# startracker.net
KiCad netlist of a schematic drawn in EasyEDA
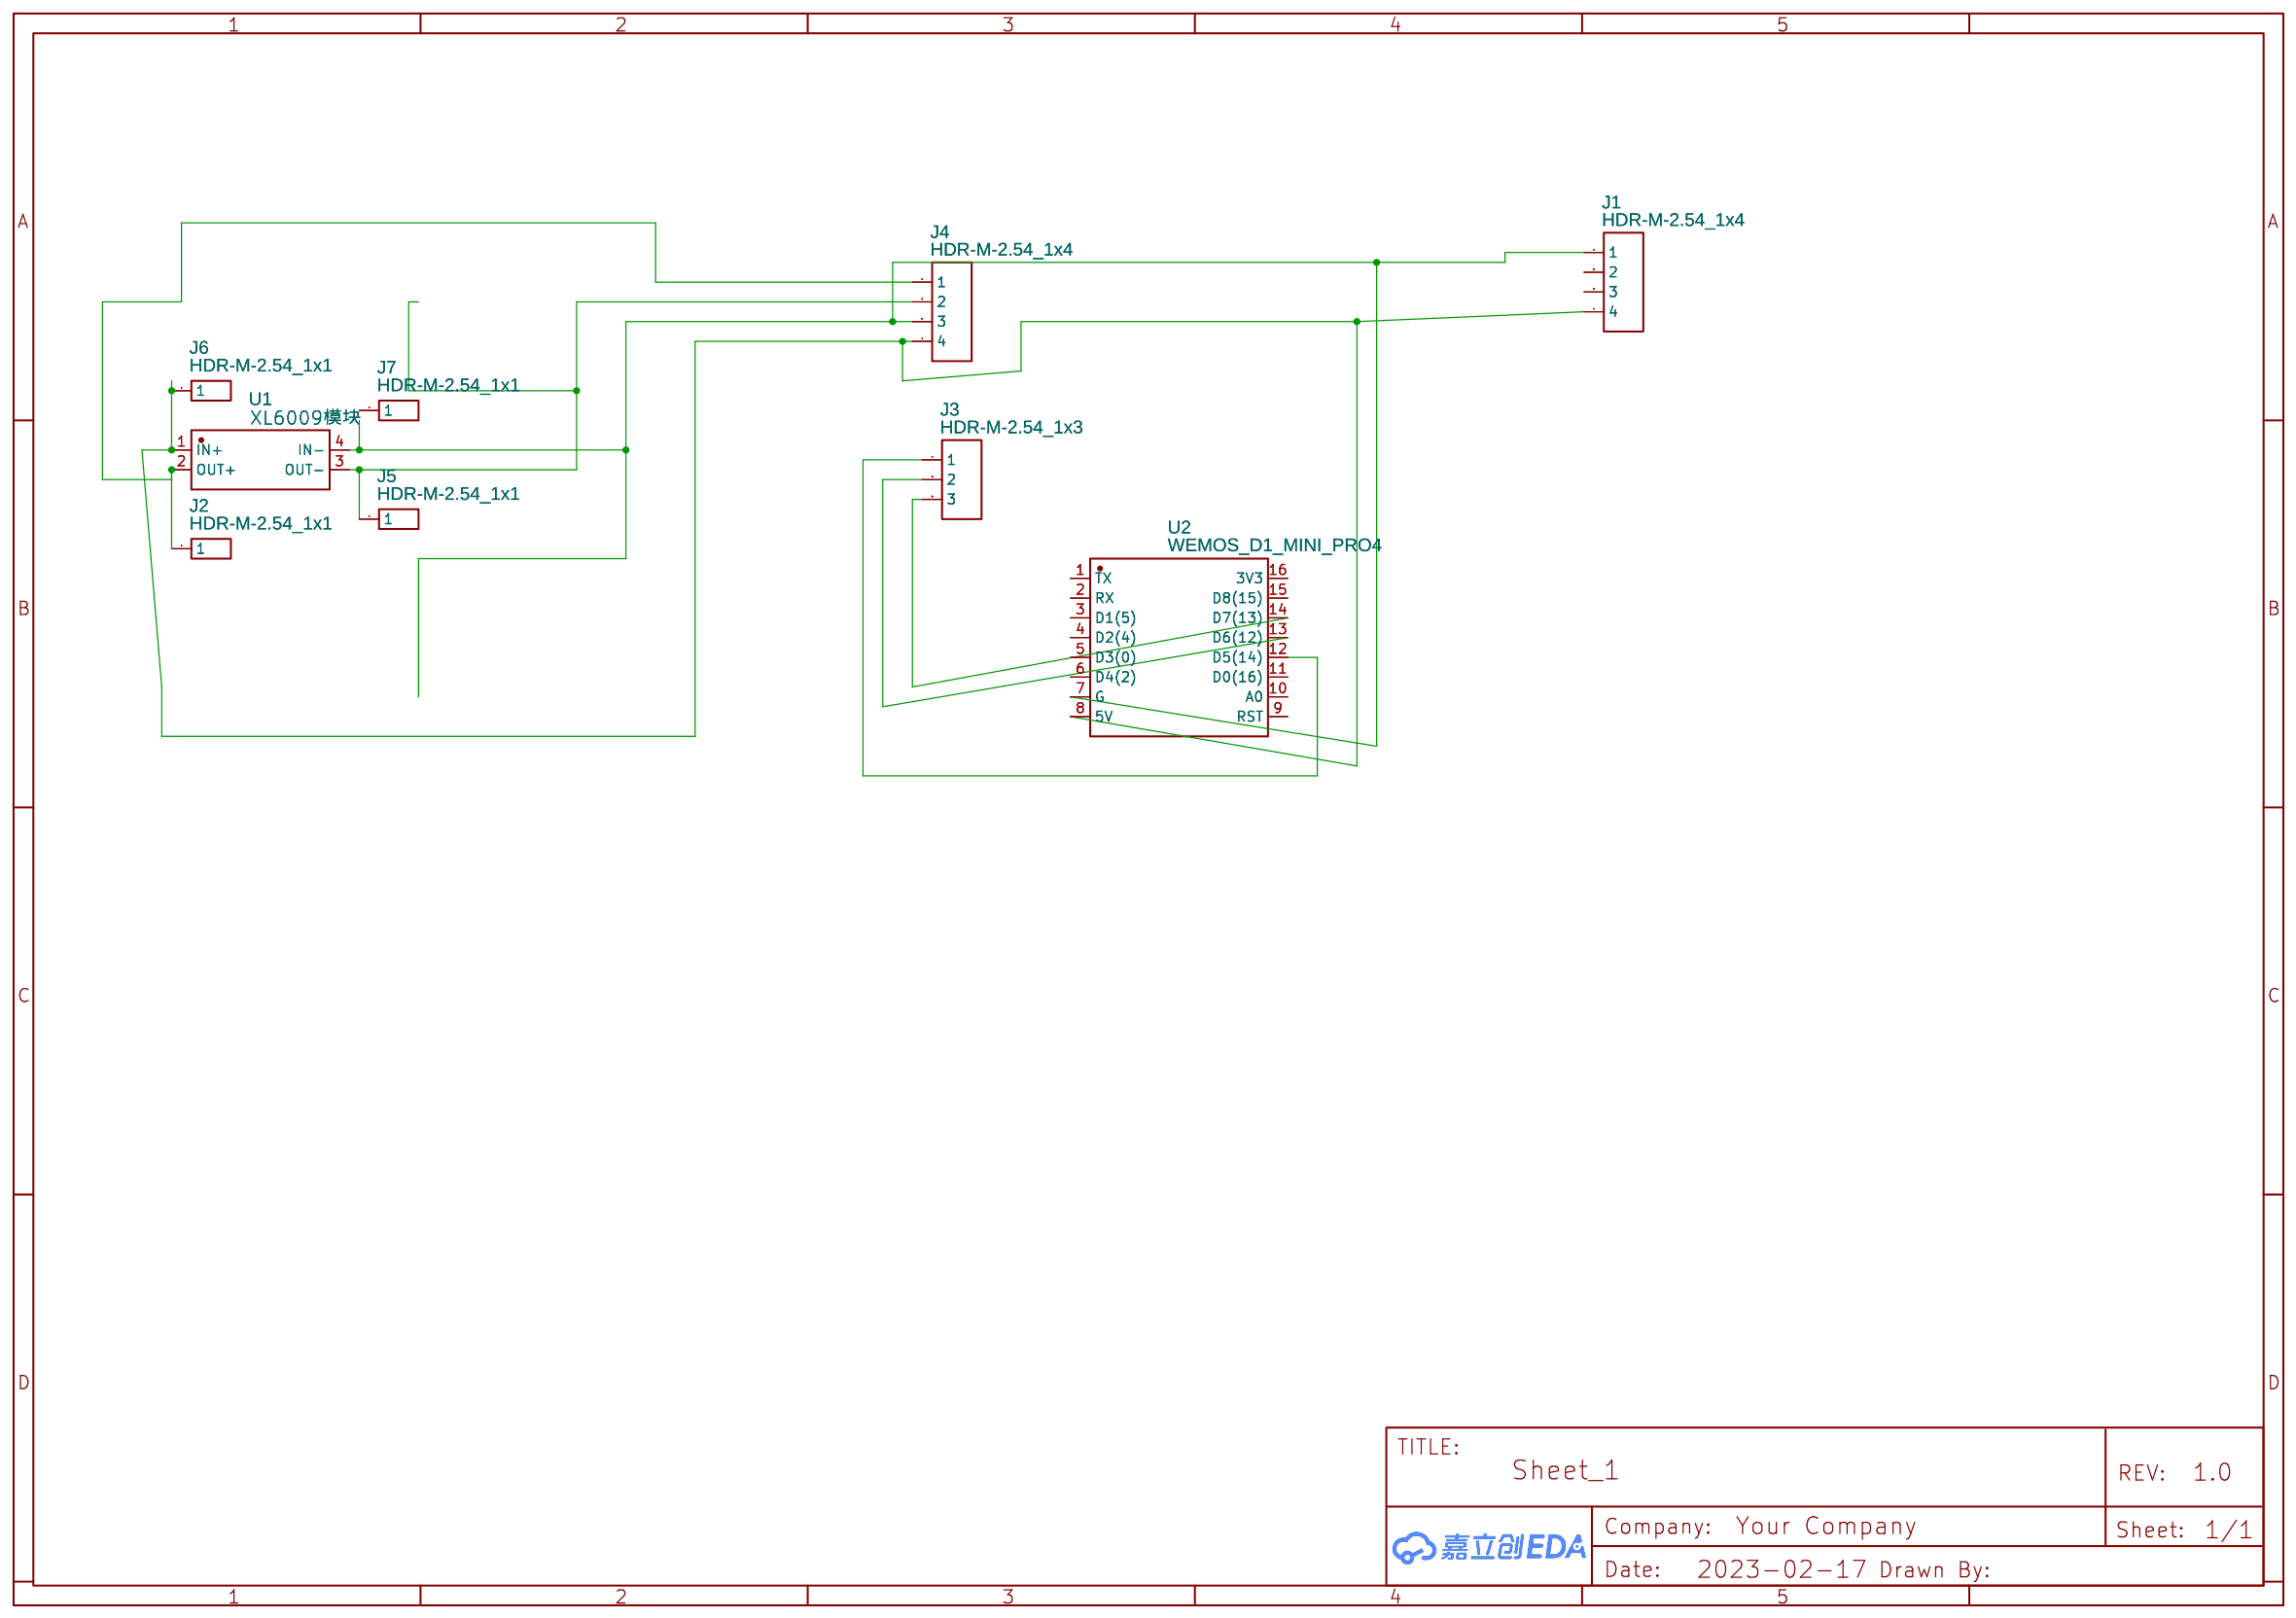
[diagram p0: schematic sheet]

(export (version "E")
  (design (tool "Eeschema 10.0.6"))
  (components
    (comp (ref "J1")
      (value "HDR-M-2.54_1x4")
      (fields (field (name "BOM_Supplier Part") "C124378"))
      (libsource (lib "") (part "HDR-M-2.54_1x4"))
    )
    (comp (ref "J2")
      (value "HDR-M-2.54_1x1")
      (fields (field (name "BOM_Supplier Part") "C81276"))
      (libsource (lib "") (part "HDR-M-2.54_1x1"))
    )
    (comp (ref "J3")
      (value "HDR-M-2.54_1x3")
      (fields (field (name "BOM_Supplier Part") "C180248"))
      (libsource (lib "") (part "HDR-M-2.54_1x3"))
    )
    (comp (ref "J4")
      (value "HDR-M-2.54_1x4")
      (fields (field (name "BOM_Supplier Part") "C124378"))
      (libsource (lib "") (part "HDR-M-2.54_1x4"))
    )
    (comp (ref "J5")
      (value "HDR-M-2.54_1x1")
      (fields (field (name "BOM_Supplier Part") "C81276"))
      (libsource (lib "") (part "HDR-M-2.54_1x1"))
    )
    (comp (ref "J6")
      (value "HDR-M-2.54_1x1")
      (fields (field (name "BOM_Supplier Part") "C81276"))
      (libsource (lib "") (part "HDR-M-2.54_1x1"))
    )
    (comp (ref "J7")
      (value "HDR-M-2.54_1x1")
      (fields (field (name "BOM_Supplier Part") "C81276"))
      (libsource (lib "") (part "HDR-M-2.54_1x1"))
    )
    (comp (ref "U1")
      (value "XL6009模块")
      (fields (field (name "BOM_Manufacturer Part") "xl6009模块") (field (name "BOM_Supplier Part") "C2908146"))
      (libsource (lib "") (part "XL6009模块"))
    )
    (comp (ref "U2")
      (value "WEMOS_D1_MINI_PRO4")
      (fields
        (field (name "BOM_Manufacturer Part") "Wemos_D1_mini_Pro4")
        (field (name "BOM_Supplier Part") "C2837266")
      )
      (libsource (lib "") (part "WEMOS_D1_MINI_PRO4"))
    )
  )
  (nets
    (net (code "1") (name "Net-(U1-IN+)") (class "Default")
      (node (ref "J1") (pin "4") (pinfunction "4_4") (pintype "unspecified"))
      (node (ref "J4") (pin "4") (pinfunction "4_4") (pintype "unspecified"))
      (node (ref "J6") (pin "1") (pinfunction "1_1") (pintype "input"))
      (node (ref "U1") (pin "1") (pinfunction "IN+_1") (pintype "unspecified"))
      (node (ref "U2") (pin "8") (pinfunction "5V_8") (pintype "unspecified"))
    )
    (net (code "2") (name "Net-(U1-IN-)") (class "Default")
      (node (ref "J1") (pin "1") (pinfunction "1_1") (pintype "unspecified"))
      (node (ref "J4") (pin "3") (pinfunction "3_3") (pintype "unspecified"))
      (node (ref "U1") (pin "4") (pinfunction "IN-_4") (pintype "unspecified"))
      (node (ref "U2") (pin "7") (pinfunction "G_7") (pintype "unspecified"))
    )
    (net (code "3") (name "Net-(U1-OUT+)") (class "Default")
      (node (ref "J2") (pin "1") (pinfunction "1_1") (pintype "input"))
      (node (ref "J4") (pin "1") (pinfunction "1_1") (pintype "unspecified"))
      (node (ref "U1") (pin "2") (pinfunction "OUT+_2") (pintype "unspecified"))
    )
    (net (code "4") (name "Net-(U1-OUT-)") (class "Default")
      (node (ref "J4") (pin "2") (pinfunction "2_2") (pintype "unspecified"))
      (node (ref "J5") (pin "1") (pinfunction "1_1") (pintype "input"))
      (node (ref "U1") (pin "3") (pinfunction "OUT-_3") (pintype "unspecified"))
    )
    (net (code "5") (name "Net-(U2-D5(14))") (class "Default")
      (node (ref "J3") (pin "1") (pinfunction "1_1") (pintype "input"))
      (node (ref "U2") (pin "12") (pinfunction "D5(14)_12") (pintype "unspecified"))
    )
    (net (code "6") (name "Net-(U2-D6(12))") (class "Default")
      (node (ref "J3") (pin "2") (pinfunction "2_2") (pintype "input"))
      (node (ref "U2") (pin "13") (pinfunction "D6(12)_13") (pintype "unspecified"))
    )
    (net (code "7") (name "Net-(U2-D7(13))") (class "Default")
      (node (ref "J3") (pin "3") (pinfunction "3_3") (pintype "input"))
      (node (ref "U2") (pin "14") (pinfunction "D7(13)_14") (pintype "unspecified"))
    )
    (net (code "8") (name "unconnected-(J1-Pad2)") (class "Default")
      (node (ref "J1") (pin "2") (pinfunction "2_2") (pintype "unspecified"))
    )
    (net (code "9") (name "unconnected-(J1-Pad3)") (class "Default")
      (node (ref "J1") (pin "3") (pinfunction "3_3") (pintype "unspecified"))
    )
    (net (code "10") (name "unconnected-(J7-Pad1)") (class "Default")
      (node (ref "J7") (pin "1") (pinfunction "1_1") (pintype "input"))
    )
    (net (code "11") (name "unconnected-(U2-3V3-Pad16)") (class "Default")
      (node (ref "U2") (pin "16") (pinfunction "3V3_16") (pintype "unspecified"))
    )
    (net (code "12") (name "unconnected-(U2-A0-Pad10)") (class "Default")
      (node (ref "U2") (pin "10") (pinfunction "A0_10") (pintype "unspecified"))
    )
    (net (code "13") (name "unconnected-(U2-D0(16)-Pad11)") (class "Default")
      (node (ref "U2") (pin "11") (pinfunction "D0(16)_11") (pintype "unspecified"))
    )
    (net (code "14") (name "unconnected-(U2-D1(5)-Pad3)") (class "Default")
      (node (ref "U2") (pin "3") (pinfunction "D1(5)_3") (pintype "unspecified"))
    )
    (net (code "15") (name "unconnected-(U2-D2(4)-Pad4)") (class "Default")
      (node (ref "U2") (pin "4") (pinfunction "D2(4)_4") (pintype "unspecified"))
    )
    (net (code "16") (name "unconnected-(U2-D3(0)-Pad5)") (class "Default")
      (node (ref "U2") (pin "5") (pinfunction "D3(0)_5") (pintype "unspecified"))
    )
    (net (code "17") (name "unconnected-(U2-D4(2)-Pad6)") (class "Default")
      (node (ref "U2") (pin "6") (pinfunction "D4(2)_6") (pintype "unspecified"))
    )
    (net (code "18") (name "unconnected-(U2-D8(15)-Pad15)") (class "Default")
      (node (ref "U2") (pin "15") (pinfunction "D8(15)_15") (pintype "unspecified"))
    )
    (net (code "19") (name "unconnected-(U2-RST-Pad9)") (class "Default")
      (node (ref "U2") (pin "9") (pinfunction "RST_9") (pintype "unspecified"))
    )
    (net (code "20") (name "unconnected-(U2-RX-Pad2)") (class "Default")
      (node (ref "U2") (pin "2") (pinfunction "RX_2") (pintype "unspecified"))
    )
    (net (code "21") (name "unconnected-(U2-TX-Pad1)") (class "Default")
      (node (ref "U2") (pin "1") (pinfunction "TX_1") (pintype "unspecified"))
    )
  )
)
